# uv_exposure.net
KiCad netlist of a schematic drawn in EAGLE
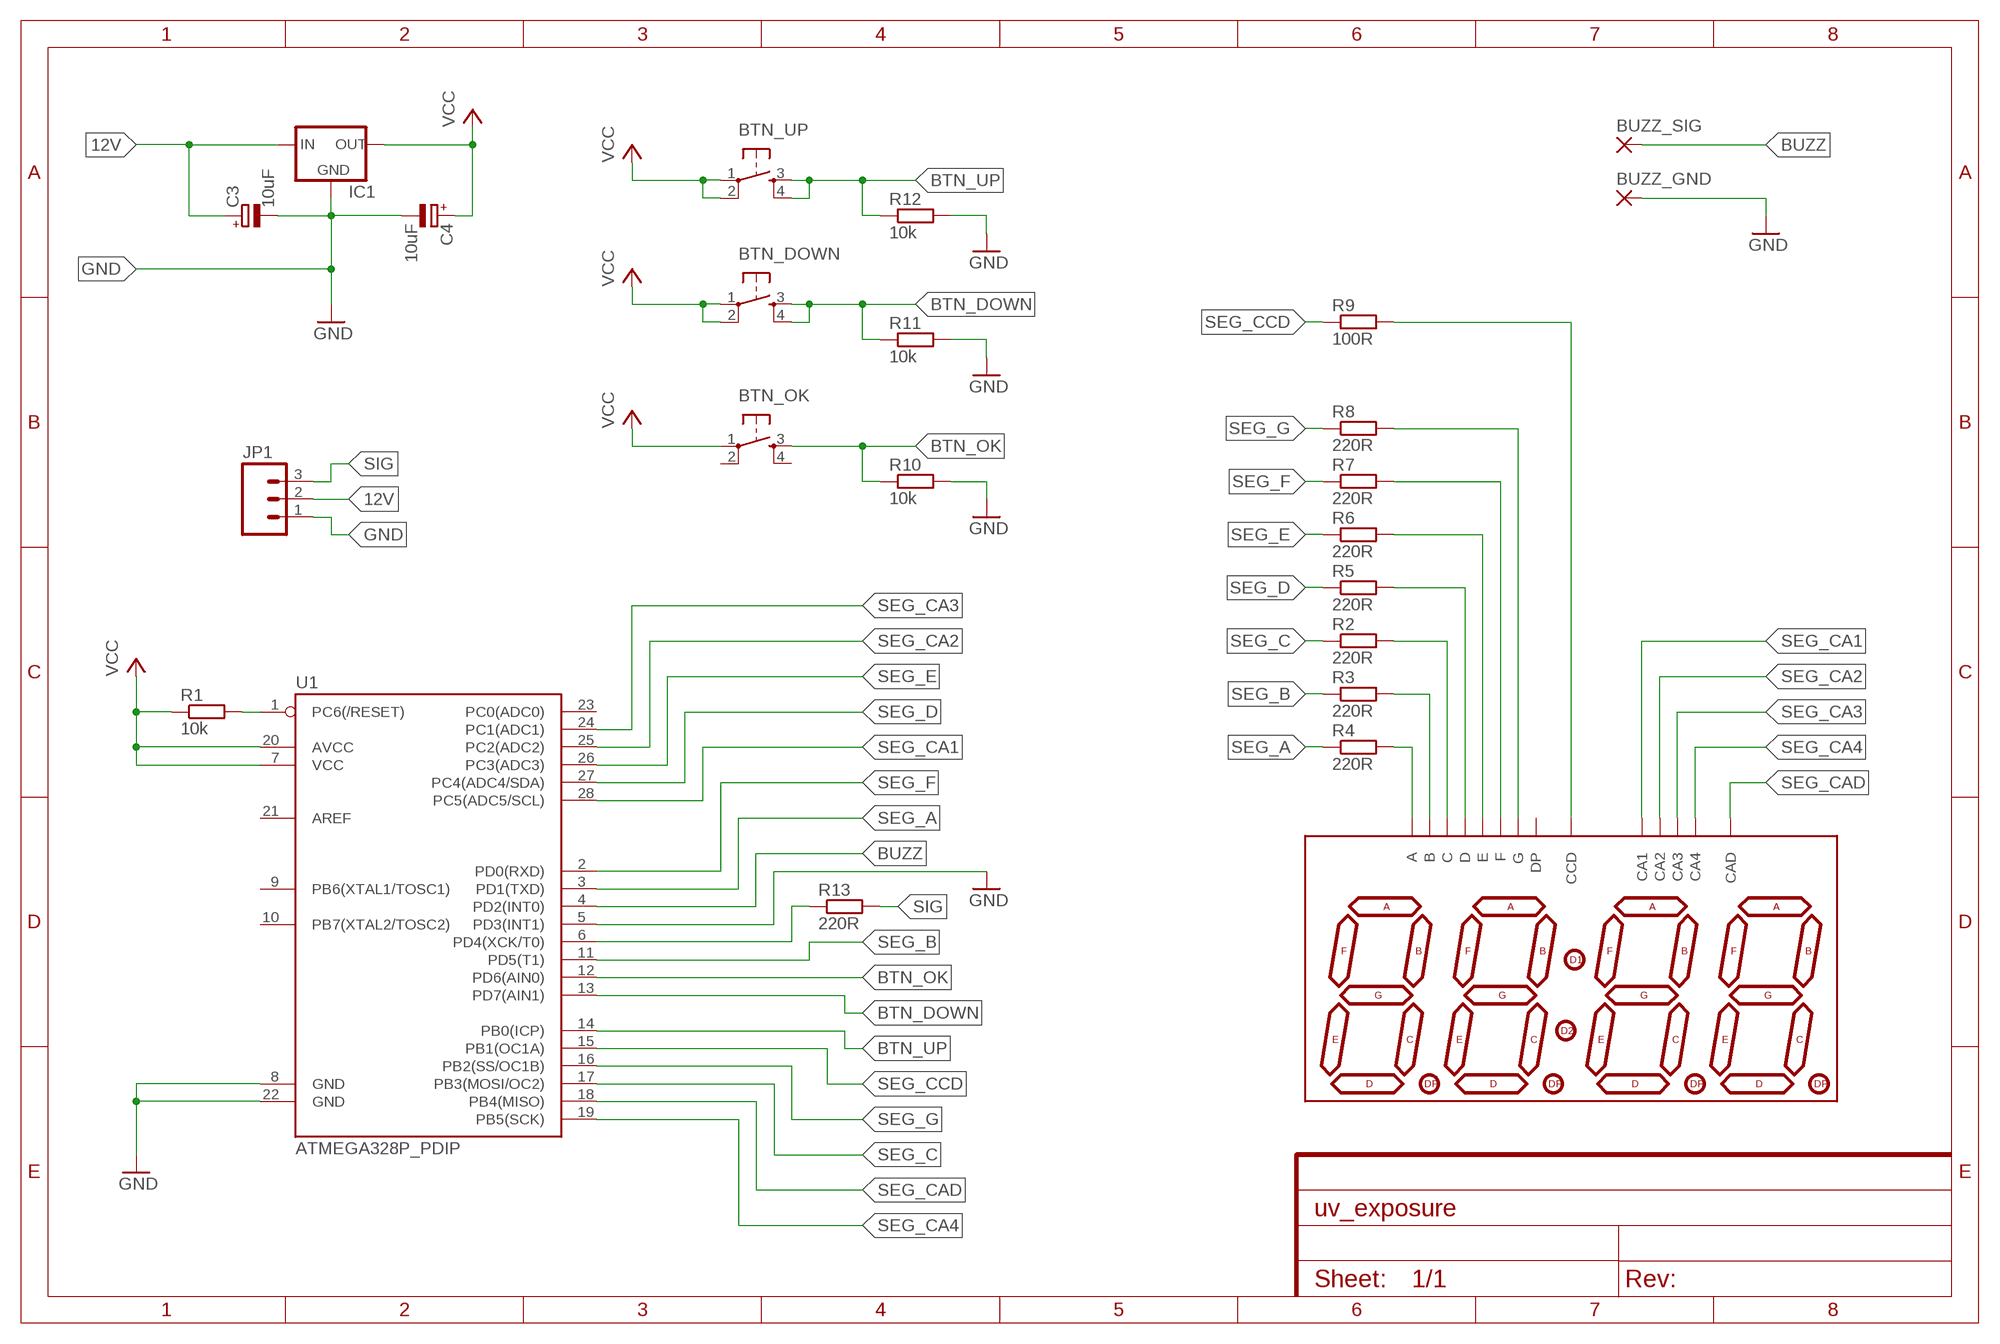
[diagram p0: schematic, sheet 1]

(export (version "E")
  (design (tool "Eeschema 10.0.6"))
  (components
    (comp (ref "BTN_DOWN")
      (value "TAC_SWITCHPTH")
      (footprint "eagle-import:TACTILE-PTH")
      (libsource (lib "eagle-import") (part "TAC_SWITCHPTH"))
    )
    (comp (ref "BTN_OK")
      (value "TAC_SWITCHPTH")
      (footprint "eagle-import:TACTILE-PTH")
      (libsource (lib "eagle-import") (part "TAC_SWITCHPTH"))
    )
    (comp (ref "BTN_UP")
      (value "TAC_SWITCHPTH")
      (footprint "eagle-import:TACTILE-PTH")
      (libsource (lib "eagle-import") (part "TAC_SWITCHPTH"))
    )
    (comp (ref "BUZZ_GND")
      (value "2,54/0,8")
      (footprint "eagle-import:2,54_0,8")
      (libsource (lib "eagle-import") (part "2,54/0,8"))
    )
    (comp (ref "BUZZ_SIG")
      (value "2,54/0,8")
      (footprint "eagle-import:2,54_0,8")
      (libsource (lib "eagle-import") (part "2,54/0,8"))
    )
    (comp (ref "C3")
      (value "10uF")
      (footprint "eagle-import:E2-5")
      (libsource (lib "eagle-import") (part "CPOL-EUE2-5"))
    )
    (comp (ref "C4")
      (value "10uF")
      (footprint "eagle-import:E2-5")
      (libsource (lib "eagle-import") (part "CPOL-EUE2-5"))
    )
    (comp (ref "IC1")
      (value "V_REG_78XXSINK")
      (footprint "eagle-import:TO220-IGO")
      (libsource (lib "eagle-import") (part "V_REG_78XXSINK"))
    )
    (comp (ref "JP1")
      (value "M03LOCK")
      (footprint "eagle-import:1X03_LOCK")
      (libsource (lib "eagle-import") (part "M03LOCK"))
    )
    (comp (ref "R1")
      (value "10k")
      (footprint "eagle-import:0207_10")
      (libsource (lib "eagle-import") (part "R-EU_0207/10"))
    )
    (comp (ref "R2")
      (value "220R")
      (footprint "eagle-import:0207_10")
      (libsource (lib "eagle-import") (part "R-EU_0207/10"))
    )
    (comp (ref "R3")
      (value "220R")
      (footprint "eagle-import:0207_10")
      (libsource (lib "eagle-import") (part "R-EU_0207/10"))
    )
    (comp (ref "R4")
      (value "220R")
      (footprint "eagle-import:0207_10")
      (libsource (lib "eagle-import") (part "R-EU_0207/10"))
    )
    (comp (ref "R5")
      (value "220R")
      (footprint "eagle-import:0207_10")
      (libsource (lib "eagle-import") (part "R-EU_0207/10"))
    )
    (comp (ref "R6")
      (value "220R")
      (footprint "eagle-import:0207_10")
      (libsource (lib "eagle-import") (part "R-EU_0207/10"))
    )
    (comp (ref "R7")
      (value "220R")
      (footprint "eagle-import:0207_10")
      (libsource (lib "eagle-import") (part "R-EU_0207/10"))
    )
    (comp (ref "R8")
      (value "220R")
      (footprint "eagle-import:0207_10")
      (libsource (lib "eagle-import") (part "R-EU_0207/10"))
    )
    (comp (ref "R9")
      (value "100R")
      (footprint "eagle-import:0207_10")
      (libsource (lib "eagle-import") (part "R-EU_0207/10"))
    )
    (comp (ref "R10")
      (value "10k")
      (footprint "eagle-import:0207_10")
      (libsource (lib "eagle-import") (part "R-EU_0207/10"))
    )
    (comp (ref "R11")
      (value "10k")
      (footprint "eagle-import:0207_10")
      (libsource (lib "eagle-import") (part "R-EU_0207/10"))
    )
    (comp (ref "R12")
      (value "10k")
      (footprint "eagle-import:0207_10")
      (libsource (lib "eagle-import") (part "R-EU_0207/10"))
    )
    (comp (ref "R13")
      (value "220R")
      (footprint "eagle-import:0207_10")
      (libsource (lib "eagle-import") (part "R-EU_0207/10"))
    )
    (comp (ref "U$1")
      (value "5461BSDIP14")
      (footprint "eagle-import:5461BS")
      (libsource (lib "eagle-import") (part "5461BSDIP14"))
    )
    (comp (ref "U1")
      (value "ATMEGA328P_PDIP")
      (footprint "eagle-import:DIL28-3")
      (libsource (lib "eagle-import") (part "ATMEGA328P_PDIP"))
    )
  )
  (nets
    (net (code "1") (name "12V") (class "Default")
      (node (ref "C3") (pin "+") (pinfunction "+_+") (pintype "passive"))
      (node (ref "IC1") (pin "IN") (pinfunction "IN_IN") (pintype "input"))
      (node (ref "JP1") (pin "2") (pinfunction "2_2") (pintype "passive"))
    )
    (net (code "2") (name "BTN_DOWN") (class "Default")
      (node (ref "BTN_DOWN") (pin "3") (pinfunction "3_3") (pintype "passive"))
      (node (ref "BTN_DOWN") (pin "4") (pinfunction "4_4") (pintype "passive"))
      (node (ref "R11") (pin "1") (pinfunction "1_1") (pintype "passive"))
      (node (ref "U1") (pin "13") (pinfunction "PD7(AIN1)_13") (pintype "bidirectional"))
    )
    (net (code "3") (name "BTN_OK") (class "Default")
      (node (ref "BTN_OK") (pin "3") (pinfunction "3_3") (pintype "passive"))
      (node (ref "R10") (pin "1") (pinfunction "1_1") (pintype "passive"))
      (node (ref "U1") (pin "12") (pinfunction "PD6(AIN0)_12") (pintype "bidirectional"))
    )
    (net (code "4") (name "BTN_UP") (class "Default")
      (node (ref "BTN_UP") (pin "3") (pinfunction "3_3") (pintype "passive"))
      (node (ref "BTN_UP") (pin "4") (pinfunction "4_4") (pintype "passive"))
      (node (ref "R12") (pin "1") (pinfunction "1_1") (pintype "passive"))
      (node (ref "U1") (pin "14") (pinfunction "PB0(ICP)_14") (pintype "bidirectional"))
    )
    (net (code "5") (name "BUZZ") (class "Default")
      (node (ref "BUZZ_SIG") (pin "1") (pinfunction "P_1") (pintype "passive"))
      (node (ref "U1") (pin "4") (pinfunction "PD2(INT0)_4") (pintype "bidirectional"))
    )
    (net (code "6") (name "GND") (class "Default")
      (node (ref "BUZZ_GND") (pin "1") (pinfunction "P_1") (pintype "passive"))
      (node (ref "C3") (pin "-") (pinfunction "-_-") (pintype "passive"))
      (node (ref "C4") (pin "-") (pinfunction "-_-") (pintype "passive"))
      (node (ref "IC1") (pin "GND") (pinfunction "GND_GND") (pintype "input"))
      (node (ref "JP1") (pin "1") (pinfunction "1_1") (pintype "passive"))
      (node (ref "R10") (pin "2") (pinfunction "2_2") (pintype "passive"))
      (node (ref "R11") (pin "2") (pinfunction "2_2") (pintype "passive"))
      (node (ref "R12") (pin "2") (pinfunction "2_2") (pintype "passive"))
      (node (ref "U1") (pin "22") (pinfunction "GND_22") (pintype "bidirectional"))
      (node (ref "U1") (pin "5") (pinfunction "PD3(INT1)_5") (pintype "bidirectional"))
      (node (ref "U1") (pin "8") (pinfunction "GND_8") (pintype "bidirectional"))
    )
    (net (code "7") (name "Net-(U$1-A)") (class "Default")
      (node (ref "R4") (pin "2") (pinfunction "2_2") (pintype "passive"))
      (node (ref "U$1") (pin "13") (pinfunction "A_13") (pintype "bidirectional"))
    )
    (net (code "8") (name "Net-(U$1-B)") (class "Default")
      (node (ref "R3") (pin "2") (pinfunction "2_2") (pintype "passive"))
      (node (ref "U$1") (pin "9") (pinfunction "B_9") (pintype "bidirectional"))
    )
    (net (code "9") (name "Net-(U$1-C)") (class "Default")
      (node (ref "R2") (pin "2") (pinfunction "2_2") (pintype "passive"))
      (node (ref "U$1") (pin "4") (pinfunction "C_4") (pintype "bidirectional"))
    )
    (net (code "10") (name "Net-(U$1-CCD)") (class "Default")
      (node (ref "R9") (pin "2") (pinfunction "2_2") (pintype "passive"))
      (node (ref "U$1") (pin "8") (pinfunction "CCD_8") (pintype "bidirectional"))
    )
    (net (code "11") (name "Net-(U$1-D)") (class "Default")
      (node (ref "R5") (pin "2") (pinfunction "2_2") (pintype "passive"))
      (node (ref "U$1") (pin "2") (pinfunction "D_2") (pintype "bidirectional"))
    )
    (net (code "12") (name "Net-(U$1-E)") (class "Default")
      (node (ref "R6") (pin "2") (pinfunction "2_2") (pintype "passive"))
      (node (ref "U$1") (pin "1") (pinfunction "E_1") (pintype "bidirectional"))
    )
    (net (code "13") (name "Net-(U$1-F)") (class "Default")
      (node (ref "R7") (pin "2") (pinfunction "2_2") (pintype "passive"))
      (node (ref "U$1") (pin "12") (pinfunction "F_12") (pintype "bidirectional"))
    )
    (net (code "14") (name "Net-(U$1-G)") (class "Default")
      (node (ref "R8") (pin "2") (pinfunction "2_2") (pintype "passive"))
      (node (ref "U$1") (pin "5") (pinfunction "G_5") (pintype "bidirectional"))
    )
    (net (code "15") (name "Net-(U1-PC6({slash}RESET))") (class "Default")
      (node (ref "R1") (pin "2") (pinfunction "2_2") (pintype "passive"))
      (node (ref "U1") (pin "1") (pinfunction "PC6(/RESET)_1") (pintype "bidirectional"))
    )
    (net (code "16") (name "Net-(U1-PD4(XCK{slash}T0))") (class "Default")
      (node (ref "R13") (pin "1") (pinfunction "1_1") (pintype "passive"))
      (node (ref "U1") (pin "6") (pinfunction "PD4(XCK/T0)_6") (pintype "bidirectional"))
    )
    (net (code "17") (name "SEG_A") (class "Default")
      (node (ref "R4") (pin "1") (pinfunction "1_1") (pintype "passive"))
      (node (ref "U1") (pin "3") (pinfunction "PD1(TXD)_3") (pintype "bidirectional"))
    )
    (net (code "18") (name "SEG_B") (class "Default")
      (node (ref "R3") (pin "1") (pinfunction "1_1") (pintype "passive"))
      (node (ref "U1") (pin "11") (pinfunction "PD5(T1)_11") (pintype "bidirectional"))
    )
    (net (code "19") (name "SEG_C") (class "Default")
      (node (ref "R2") (pin "1") (pinfunction "1_1") (pintype "passive"))
      (node (ref "U1") (pin "17") (pinfunction "PB3(MOSI/OC2)_17") (pintype "bidirectional"))
    )
    (net (code "20") (name "SEG_CA1") (class "Default")
      (node (ref "U$1") (pin "14") (pinfunction "CA1_14") (pintype "bidirectional"))
      (node (ref "U1") (pin "28") (pinfunction "PC5(ADC5/SCL)_28") (pintype "bidirectional"))
    )
    (net (code "21") (name "SEG_CA2") (class "Default")
      (node (ref "U$1") (pin "11") (pinfunction "CA2_11") (pintype "bidirectional"))
      (node (ref "U1") (pin "25") (pinfunction "PC2(ADC2)_25") (pintype "bidirectional"))
    )
    (net (code "22") (name "SEG_CA3") (class "Default")
      (node (ref "U$1") (pin "10") (pinfunction "CA3_10") (pintype "bidirectional"))
      (node (ref "U1") (pin "24") (pinfunction "PC1(ADC1)_24") (pintype "bidirectional"))
    )
    (net (code "23") (name "SEG_CA4") (class "Default")
      (node (ref "U$1") (pin "6") (pinfunction "CA4_6") (pintype "bidirectional"))
      (node (ref "U1") (pin "19") (pinfunction "PB5(SCK)_19") (pintype "bidirectional"))
    )
    (net (code "24") (name "SEG_CAD") (class "Default")
      (node (ref "U$1") (pin "7") (pinfunction "CAD_7") (pintype "bidirectional"))
      (node (ref "U1") (pin "18") (pinfunction "PB4(MISO)_18") (pintype "bidirectional"))
    )
    (net (code "25") (name "SEG_CCD") (class "Default")
      (node (ref "R9") (pin "1") (pinfunction "1_1") (pintype "passive"))
      (node (ref "U1") (pin "15") (pinfunction "PB1(OC1A)_15") (pintype "bidirectional"))
    )
    (net (code "26") (name "SEG_D") (class "Default")
      (node (ref "R5") (pin "1") (pinfunction "1_1") (pintype "passive"))
      (node (ref "U1") (pin "27") (pinfunction "PC4(ADC4/SDA)_27") (pintype "bidirectional"))
    )
    (net (code "27") (name "SEG_E") (class "Default")
      (node (ref "R6") (pin "1") (pinfunction "1_1") (pintype "passive"))
      (node (ref "U1") (pin "26") (pinfunction "PC3(ADC3)_26") (pintype "bidirectional"))
    )
    (net (code "28") (name "SEG_F") (class "Default")
      (node (ref "R7") (pin "1") (pinfunction "1_1") (pintype "passive"))
      (node (ref "U1") (pin "2") (pinfunction "PD0(RXD)_2") (pintype "bidirectional"))
    )
    (net (code "29") (name "SEG_G") (class "Default")
      (node (ref "R8") (pin "1") (pinfunction "1_1") (pintype "passive"))
      (node (ref "U1") (pin "16") (pinfunction "PB2(SS/OC1B)_16") (pintype "bidirectional"))
    )
    (net (code "30") (name "SIG") (class "Default")
      (node (ref "JP1") (pin "3") (pinfunction "3_3") (pintype "passive"))
      (node (ref "R13") (pin "2") (pinfunction "2_2") (pintype "passive"))
    )
    (net (code "31") (name "VCC") (class "Default")
      (node (ref "BTN_DOWN") (pin "1") (pinfunction "1_1") (pintype "passive"))
      (node (ref "BTN_DOWN") (pin "2") (pinfunction "2_2") (pintype "passive"))
      (node (ref "BTN_OK") (pin "1") (pinfunction "1_1") (pintype "passive"))
      (node (ref "BTN_UP") (pin "1") (pinfunction "1_1") (pintype "passive"))
      (node (ref "BTN_UP") (pin "2") (pinfunction "2_2") (pintype "passive"))
      (node (ref "C4") (pin "+") (pinfunction "+_+") (pintype "passive"))
      (node (ref "IC1") (pin "OUT") (pinfunction "OUT_OUT") (pintype "output"))
      (node (ref "R1") (pin "1") (pinfunction "1_1") (pintype "passive"))
      (node (ref "U1") (pin "20") (pinfunction "AVCC_20") (pintype "bidirectional"))
      (node (ref "U1") (pin "7") (pinfunction "VCC_7") (pintype "bidirectional"))
    )
    (net (code "32") (name "unconnected-(BTN_OK-Pad2)") (class "Default")
      (node (ref "BTN_OK") (pin "2") (pinfunction "2_2") (pintype "passive"))
    )
    (net (code "33") (name "unconnected-(BTN_OK-Pad4)") (class "Default")
      (node (ref "BTN_OK") (pin "4") (pinfunction "4_4") (pintype "passive"))
    )
    (net (code "34") (name "unconnected-(U$1-DP-Pad3)") (class "Default")
      (node (ref "U$1") (pin "3") (pinfunction "DP_3") (pintype "bidirectional"))
    )
    (net (code "35") (name "unconnected-(U1-AREF-Pad21)") (class "Default")
      (node (ref "U1") (pin "21") (pinfunction "AREF_21") (pintype "bidirectional"))
    )
    (net (code "36") (name "unconnected-(U1-PB6(XTAL1{slash}TOSC1)-Pad9)") (class "Default")
      (node (ref "U1") (pin "9") (pinfunction "PB6(XTAL1/TOSC1)_9") (pintype "bidirectional"))
    )
    (net (code "37") (name "unconnected-(U1-PB7(XTAL2{slash}TOSC2)-Pad10)") (class "Default")
      (node (ref "U1") (pin "10") (pinfunction "PB7(XTAL2/TOSC2)_10") (pintype "bidirectional"))
    )
    (net (code "38") (name "unconnected-(U1-PC0(ADC0)-Pad23)") (class "Default")
      (node (ref "U1") (pin "23") (pinfunction "PC0(ADC0)_23") (pintype "bidirectional"))
    )
  )
)
